# MDD.net
KiCad netlist of a schematic drawn in EAGLE
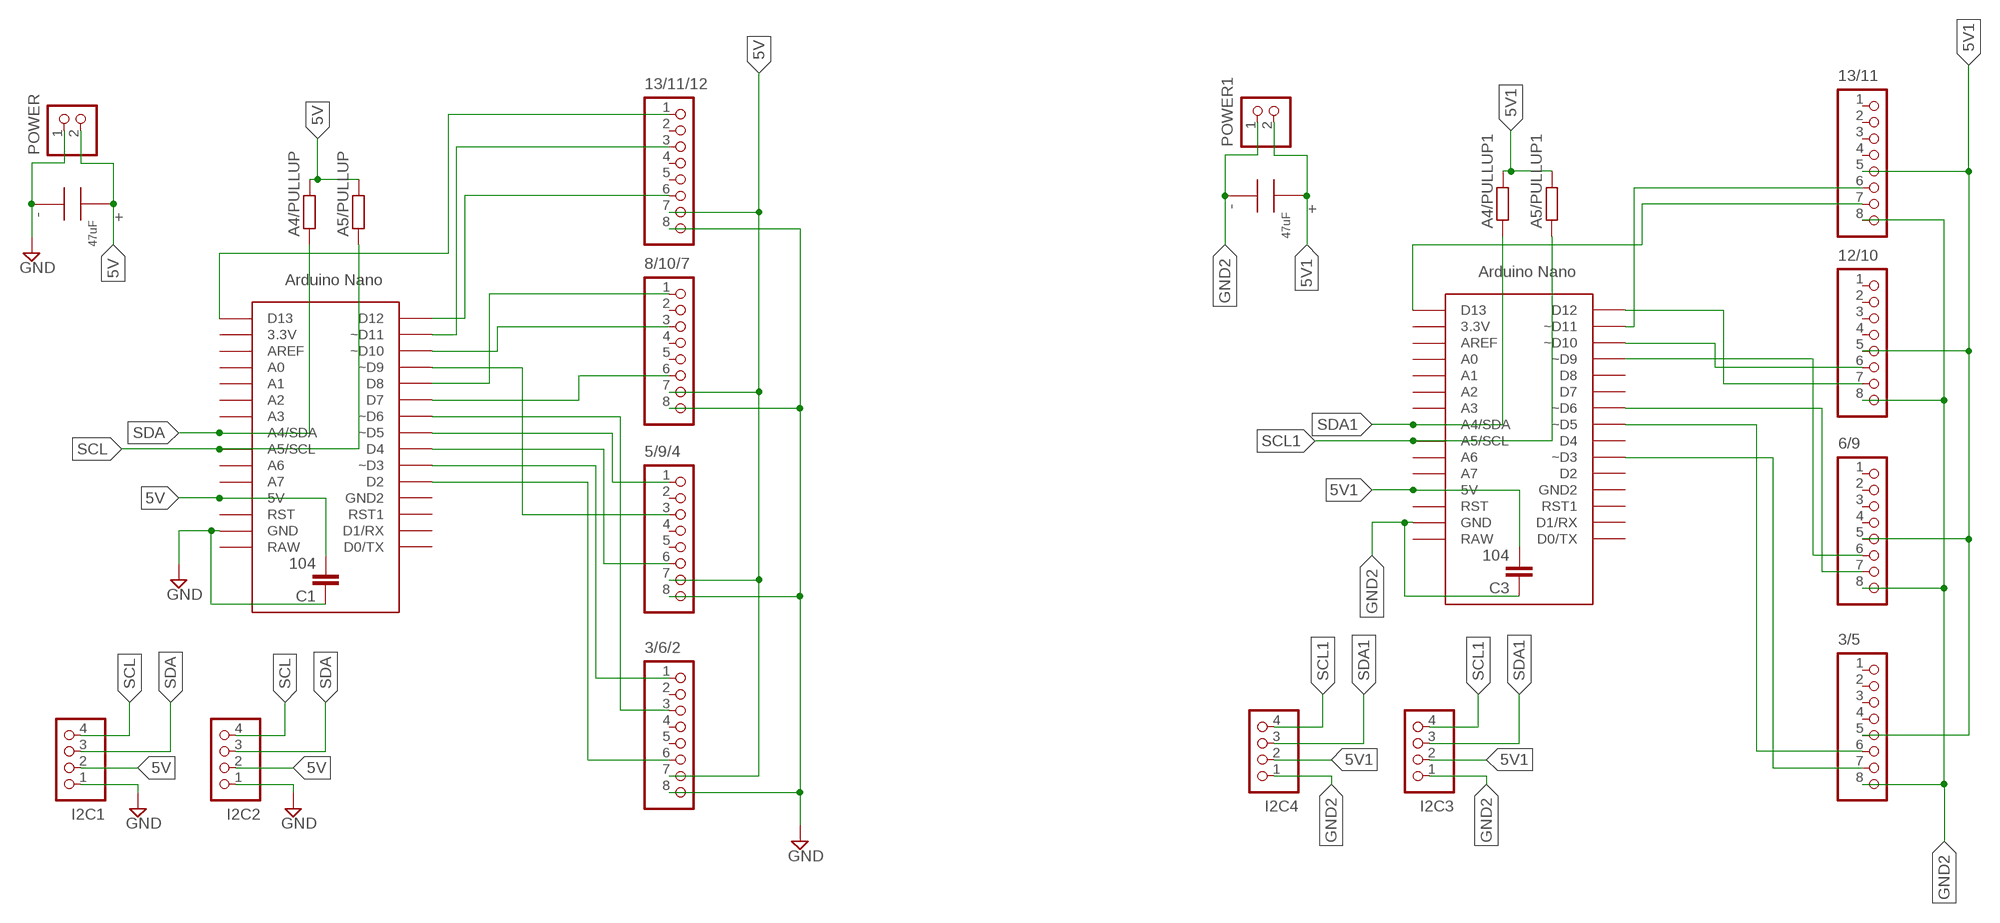
[diagram p0: schematic, sheet 1]

(export (version "E")
  (design (tool "Eeschema 10.0.6"))
  (components
    (comp (ref "3/5")
      (value "B8B-XH-A")
      (footprint "eagle-import:B8B-XH-A")
      (libsource (lib "eagle-import") (part "B8B-XH-A"))
    )
    (comp (ref "3/6/2")
      (value "B8B-XH-A")
      (footprint "eagle-import:B8B-XH-A")
      (libsource (lib "eagle-import") (part "B8B-XH-A"))
    )
    (comp (ref "5/9/4")
      (value "B8B-XH-A")
      (footprint "eagle-import:B8B-XH-A")
      (libsource (lib "eagle-import") (part "B8B-XH-A"))
    )
    (comp (ref "6/9")
      (value "B8B-XH-A")
      (footprint "eagle-import:B8B-XH-A")
      (libsource (lib "eagle-import") (part "B8B-XH-A"))
    )
    (comp (ref "8/10/7")
      (value "B8B-XH-A")
      (footprint "eagle-import:B8B-XH-A")
      (libsource (lib "eagle-import") (part "B8B-XH-A"))
    )
    (comp (ref "12/10")
      (value "B8B-XH-A")
      (footprint "eagle-import:B8B-XH-A")
      (libsource (lib "eagle-import") (part "B8B-XH-A"))
    )
    (comp (ref "13/11")
      (value "B8B-XH-A")
      (footprint "eagle-import:B8B-XH-A")
      (libsource (lib "eagle-import") (part "B8B-XH-A"))
    )
    (comp (ref "13/11/12")
      (value "B8B-XH-A")
      (footprint "eagle-import:B8B-XH-A")
      (libsource (lib "eagle-import") (part "B8B-XH-A"))
    )
    (comp (ref "A4/PULLUP")
      (value "R-EU_0204/7")
      (footprint "eagle-import:0204_7")
      (libsource (lib "eagle-import") (part "R-EU_0204/7"))
    )
    (comp (ref "A4/PULLUP1")
      (value "R-EU_0204/7")
      (footprint "eagle-import:0204_7")
      (libsource (lib "eagle-import") (part "R-EU_0204/7"))
    )
    (comp (ref "A5/PULLUP")
      (value "R-EU_0204/7")
      (footprint "eagle-import:0204_7")
      (libsource (lib "eagle-import") (part "R-EU_0204/7"))
    )
    (comp (ref "A5/PULLUP1")
      (value "R-EU_0204/7")
      (footprint "eagle-import:0204_7")
      (libsource (lib "eagle-import") (part "R-EU_0204/7"))
    )
    (comp (ref "C1")
      (value "104")
      (footprint "eagle-import:C2.5-2")
      (libsource (lib "eagle-import") (part "C2.5/2"))
    )
    (comp (ref "C2")
      (value "47uF")
      (footprint "eagle-import:C_47UF")
      (libsource (lib "eagle-import") (part "C_47UF"))
    )
    (comp (ref "C3")
      (value "104")
      (footprint "eagle-import:C2.5-2")
      (libsource (lib "eagle-import") (part "C2.5/2"))
    )
    (comp (ref "C4")
      (value "47uF")
      (footprint "eagle-import:C_47UF")
      (libsource (lib "eagle-import") (part "C_47UF"))
    )
    (comp (ref "I2C1")
      (value "B4B-XH-A")
      (footprint "eagle-import:B4B-XH-A")
      (libsource (lib "eagle-import") (part "B4B-XH-A"))
    )
    (comp (ref "I2C2")
      (value "B4B-XH-A")
      (footprint "eagle-import:B4B-XH-A")
      (libsource (lib "eagle-import") (part "B4B-XH-A"))
    )
    (comp (ref "I2C3")
      (value "B4B-XH-A")
      (footprint "eagle-import:B4B-XH-A")
      (libsource (lib "eagle-import") (part "B4B-XH-A"))
    )
    (comp (ref "I2C4")
      (value "B4B-XH-A")
      (footprint "eagle-import:B4B-XH-A")
      (libsource (lib "eagle-import") (part "B4B-XH-A"))
    )
    (comp (ref "NANO")
      (value "NANO")
      (footprint "eagle-import:NANO")
      (libsource (lib "eagle-import") (part "NANO"))
    )
    (comp (ref "NANO1")
      (value "NANO")
      (footprint "eagle-import:NANO")
      (libsource (lib "eagle-import") (part "NANO"))
    )
    (comp (ref "POWER")
      (value "B2B-XH-A")
      (footprint "eagle-import:B2B-XH-A")
      (libsource (lib "eagle-import") (part "B2B-XH-A"))
    )
    (comp (ref "POWER1")
      (value "B2B-XH-A")
      (footprint "eagle-import:B2B-XH-A")
      (libsource (lib "eagle-import") (part "B2B-XH-A"))
    )
  )
  (nets
    (net (code "1") (name "5V") (class "Default")
      (node (ref "13/11/12") (pin "7") (pinfunction "7_7") (pintype "passive"))
      (node (ref "3/6/2") (pin "7") (pinfunction "7_7") (pintype "passive"))
      (node (ref "5/9/4") (pin "7") (pinfunction "7_7") (pintype "passive"))
      (node (ref "8/10/7") (pin "7") (pinfunction "7_7") (pintype "passive"))
      (node (ref "A4/PULLUP") (pin "2") (pinfunction "2_2") (pintype "passive"))
      (node (ref "A5/PULLUP") (pin "2") (pinfunction "2_2") (pintype "passive"))
      (node (ref "C1") (pin "2") (pinfunction "2_2") (pintype "passive"))
      (node (ref "C2") (pin "+") (pinfunction "+_+") (pintype "bidirectional"))
      (node (ref "I2C1") (pin "2") (pinfunction "2_2") (pintype "passive"))
      (node (ref "I2C2") (pin "2") (pinfunction "2_2") (pintype "passive"))
      (node (ref "NANO") (pin "5V") (pinfunction "5V_5V") (pintype "bidirectional"))
      (node (ref "POWER") (pin "2") (pinfunction "VCC_2") (pintype "passive"))
    )
    (net (code "2") (name "5V1") (class "Default")
      (node (ref "12/10") (pin "5") (pinfunction "5_5") (pintype "passive"))
      (node (ref "13/11") (pin "5") (pinfunction "5_5") (pintype "passive"))
      (node (ref "3/5") (pin "5") (pinfunction "5_5") (pintype "passive"))
      (node (ref "6/9") (pin "5") (pinfunction "5_5") (pintype "passive"))
      (node (ref "A4/PULLUP1") (pin "2") (pinfunction "2_2") (pintype "passive"))
      (node (ref "A5/PULLUP1") (pin "2") (pinfunction "2_2") (pintype "passive"))
      (node (ref "C3") (pin "2") (pinfunction "2_2") (pintype "passive"))
      (node (ref "C4") (pin "+") (pinfunction "+_+") (pintype "bidirectional"))
      (node (ref "I2C3") (pin "2") (pinfunction "2_2") (pintype "passive"))
      (node (ref "I2C4") (pin "2") (pinfunction "2_2") (pintype "passive"))
      (node (ref "NANO1") (pin "5V") (pinfunction "5V_5V") (pintype "bidirectional"))
      (node (ref "POWER1") (pin "2") (pinfunction "VCC_2") (pintype "passive"))
    )
    (net (code "3") (name "GND") (class "Default")
      (node (ref "13/11/12") (pin "8") (pinfunction "8_8") (pintype "passive"))
      (node (ref "3/6/2") (pin "8") (pinfunction "8_8") (pintype "passive"))
      (node (ref "5/9/4") (pin "8") (pinfunction "8_8") (pintype "passive"))
      (node (ref "8/10/7") (pin "8") (pinfunction "8_8") (pintype "passive"))
      (node (ref "C1") (pin "1") (pinfunction "1_1") (pintype "passive"))
      (node (ref "C2") (pin "-") (pinfunction "-_-") (pintype "bidirectional"))
      (node (ref "I2C1") (pin "1") (pinfunction "1_1") (pintype "passive"))
      (node (ref "I2C2") (pin "1") (pinfunction "1_1") (pintype "passive"))
      (node (ref "NANO") (pin "GND") (pinfunction "GND_GND") (pintype "bidirectional"))
      (node (ref "POWER") (pin "1") (pinfunction "GND_1") (pintype "passive"))
    )
    (net (code "4") (name "GND2") (class "Default")
      (node (ref "12/10") (pin "8") (pinfunction "8_8") (pintype "passive"))
      (node (ref "13/11") (pin "8") (pinfunction "8_8") (pintype "passive"))
      (node (ref "3/5") (pin "8") (pinfunction "8_8") (pintype "passive"))
      (node (ref "6/9") (pin "8") (pinfunction "8_8") (pintype "passive"))
      (node (ref "C3") (pin "1") (pinfunction "1_1") (pintype "passive"))
      (node (ref "C4") (pin "-") (pinfunction "-_-") (pintype "bidirectional"))
      (node (ref "I2C3") (pin "1") (pinfunction "1_1") (pintype "passive"))
      (node (ref "I2C4") (pin "1") (pinfunction "1_1") (pintype "passive"))
      (node (ref "NANO1") (pin "GND") (pinfunction "GND_GND") (pintype "bidirectional"))
      (node (ref "POWER1") (pin "1") (pinfunction "GND_1") (pintype "passive"))
    )
    (net (code "5") (name "Net-(3/6/2-Pad6)") (class "Default")
      (node (ref "3/6/2") (pin "6") (pinfunction "6_6") (pintype "passive"))
      (node (ref "NANO") (pin "D2") (pinfunction "D2_D2") (pintype "bidirectional"))
    )
    (net (code "6") (name "Net-(5/9/4-Pad6)") (class "Default")
      (node (ref "5/9/4") (pin "6") (pinfunction "6_6") (pintype "passive"))
      (node (ref "NANO") (pin "D4") (pinfunction "D4_D4") (pintype "bidirectional"))
    )
    (net (code "7") (name "Net-(8/10/7-Pad1)") (class "Default")
      (node (ref "8/10/7") (pin "1") (pinfunction "1_1") (pintype "passive"))
      (node (ref "NANO") (pin "D8") (pinfunction "D8_D8") (pintype "bidirectional"))
    )
    (net (code "8") (name "Net-(8/10/7-Pad6)") (class "Default")
      (node (ref "8/10/7") (pin "6") (pinfunction "6_6") (pintype "passive"))
      (node (ref "NANO") (pin "D7") (pinfunction "D7_D7") (pintype "bidirectional"))
    )
    (net (code "9") (name "Net-(12/10-Pad7)") (class "Default")
      (node (ref "12/10") (pin "7") (pinfunction "7_7") (pintype "passive"))
      (node (ref "NANO1") (pin "D12") (pinfunction "D12_D12") (pintype "bidirectional"))
    )
    (net (code "10") (name "Net-(13/11-Pad7)") (class "Default")
      (node (ref "13/11") (pin "7") (pinfunction "7_7") (pintype "passive"))
      (node (ref "NANO1") (pin "D13") (pinfunction "D13_D13") (pintype "bidirectional"))
    )
    (net (code "11") (name "Net-(13/11/12-Pad1)") (class "Default")
      (node (ref "13/11/12") (pin "1") (pinfunction "1_1") (pintype "passive"))
      (node (ref "NANO") (pin "D13") (pinfunction "D13_D13") (pintype "bidirectional"))
    )
    (net (code "12") (name "Net-(13/11/12-Pad6)") (class "Default")
      (node (ref "13/11/12") (pin "6") (pinfunction "6_6") (pintype "passive"))
      (node (ref "NANO") (pin "D12") (pinfunction "D12_D12") (pintype "bidirectional"))
    )
    (net (code "13") (name "Net-(NANO-~{D3})") (class "Default")
      (node (ref "3/6/2") (pin "1") (pinfunction "1_1") (pintype "passive"))
      (node (ref "NANO") (pin "D3") (pinfunction "~{D3}_D3") (pintype "bidirectional"))
    )
    (net (code "14") (name "Net-(NANO-~{D5})") (class "Default")
      (node (ref "5/9/4") (pin "1") (pinfunction "1_1") (pintype "passive"))
      (node (ref "NANO") (pin "D5") (pinfunction "~{D5}_D5") (pintype "bidirectional"))
    )
    (net (code "15") (name "Net-(NANO-~{D6})") (class "Default")
      (node (ref "3/6/2") (pin "3") (pinfunction "3_3") (pintype "passive"))
      (node (ref "NANO") (pin "D6") (pinfunction "~{D6}_D6") (pintype "bidirectional"))
    )
    (net (code "16") (name "Net-(NANO-~{D9})") (class "Default")
      (node (ref "5/9/4") (pin "3") (pinfunction "3_3") (pintype "passive"))
      (node (ref "NANO") (pin "D9") (pinfunction "~{D9}_D9") (pintype "bidirectional"))
    )
    (net (code "17") (name "Net-(NANO-~{D10})") (class "Default")
      (node (ref "8/10/7") (pin "3") (pinfunction "3_3") (pintype "passive"))
      (node (ref "NANO") (pin "D10") (pinfunction "~{D10}_D10") (pintype "bidirectional"))
    )
    (net (code "18") (name "Net-(NANO-~{D11})") (class "Default")
      (node (ref "13/11/12") (pin "3") (pinfunction "3_3") (pintype "passive"))
      (node (ref "NANO") (pin "D11") (pinfunction "~{D11}_D11") (pintype "bidirectional"))
    )
    (net (code "19") (name "Net-(NANO1-~{D3})") (class "Default")
      (node (ref "3/5") (pin "7") (pinfunction "7_7") (pintype "passive"))
      (node (ref "NANO1") (pin "D3") (pinfunction "~{D3}_D3") (pintype "bidirectional"))
    )
    (net (code "20") (name "Net-(NANO1-~{D5})") (class "Default")
      (node (ref "3/5") (pin "6") (pinfunction "6_6") (pintype "passive"))
      (node (ref "NANO1") (pin "D5") (pinfunction "~{D5}_D5") (pintype "bidirectional"))
    )
    (net (code "21") (name "Net-(NANO1-~{D6})") (class "Default")
      (node (ref "6/9") (pin "7") (pinfunction "7_7") (pintype "passive"))
      (node (ref "NANO1") (pin "D6") (pinfunction "~{D6}_D6") (pintype "bidirectional"))
    )
    (net (code "22") (name "Net-(NANO1-~{D9})") (class "Default")
      (node (ref "6/9") (pin "6") (pinfunction "6_6") (pintype "passive"))
      (node (ref "NANO1") (pin "D9") (pinfunction "~{D9}_D9") (pintype "bidirectional"))
    )
    (net (code "23") (name "Net-(NANO1-~{D10})") (class "Default")
      (node (ref "12/10") (pin "6") (pinfunction "6_6") (pintype "passive"))
      (node (ref "NANO1") (pin "D10") (pinfunction "~{D10}_D10") (pintype "bidirectional"))
    )
    (net (code "24") (name "Net-(NANO1-~{D11})") (class "Default")
      (node (ref "13/11") (pin "6") (pinfunction "6_6") (pintype "passive"))
      (node (ref "NANO1") (pin "D11") (pinfunction "~{D11}_D11") (pintype "bidirectional"))
    )
    (net (code "25") (name "SCL") (class "Default")
      (node (ref "A5/PULLUP") (pin "1") (pinfunction "1_1") (pintype "passive"))
      (node (ref "I2C1") (pin "4") (pinfunction "4_4") (pintype "passive"))
      (node (ref "I2C2") (pin "4") (pinfunction "4_4") (pintype "passive"))
      (node (ref "NANO") (pin "A5") (pinfunction "A5/SCL_A5") (pintype "bidirectional"))
    )
    (net (code "26") (name "SCL1") (class "Default")
      (node (ref "A5/PULLUP1") (pin "1") (pinfunction "1_1") (pintype "passive"))
      (node (ref "I2C3") (pin "4") (pinfunction "4_4") (pintype "passive"))
      (node (ref "I2C4") (pin "4") (pinfunction "4_4") (pintype "passive"))
      (node (ref "NANO1") (pin "A5") (pinfunction "A5/SCL_A5") (pintype "bidirectional"))
    )
    (net (code "27") (name "SDA") (class "Default")
      (node (ref "A4/PULLUP") (pin "1") (pinfunction "1_1") (pintype "passive"))
      (node (ref "I2C1") (pin "3") (pinfunction "3_3") (pintype "passive"))
      (node (ref "I2C2") (pin "3") (pinfunction "3_3") (pintype "passive"))
      (node (ref "NANO") (pin "A4") (pinfunction "A4/SDA_A4") (pintype "bidirectional"))
    )
    (net (code "28") (name "SDA1") (class "Default")
      (node (ref "A4/PULLUP1") (pin "1") (pinfunction "1_1") (pintype "passive"))
      (node (ref "I2C3") (pin "3") (pinfunction "3_3") (pintype "passive"))
      (node (ref "I2C4") (pin "3") (pinfunction "3_3") (pintype "passive"))
      (node (ref "NANO1") (pin "A4") (pinfunction "A4/SDA_A4") (pintype "bidirectional"))
    )
    (net (code "29") (name "unconnected-(3/5-Pad1)") (class "Default")
      (node (ref "3/5") (pin "1") (pinfunction "1_1") (pintype "passive"))
    )
    (net (code "30") (name "unconnected-(3/5-Pad2)") (class "Default")
      (node (ref "3/5") (pin "2") (pinfunction "2_2") (pintype "passive"))
    )
    (net (code "31") (name "unconnected-(3/5-Pad3)") (class "Default")
      (node (ref "3/5") (pin "3") (pinfunction "3_3") (pintype "passive"))
    )
    (net (code "32") (name "unconnected-(3/5-Pad4)") (class "Default")
      (node (ref "3/5") (pin "4") (pinfunction "4_4") (pintype "passive"))
    )
    (net (code "33") (name "unconnected-(3/6/2-Pad2)") (class "Default")
      (node (ref "3/6/2") (pin "2") (pinfunction "2_2") (pintype "passive"))
    )
    (net (code "34") (name "unconnected-(3/6/2-Pad4)") (class "Default")
      (node (ref "3/6/2") (pin "4") (pinfunction "4_4") (pintype "passive"))
    )
    (net (code "35") (name "unconnected-(3/6/2-Pad5)") (class "Default")
      (node (ref "3/6/2") (pin "5") (pinfunction "5_5") (pintype "passive"))
    )
    (net (code "36") (name "unconnected-(5/9/4-Pad2)") (class "Default")
      (node (ref "5/9/4") (pin "2") (pinfunction "2_2") (pintype "passive"))
    )
    (net (code "37") (name "unconnected-(5/9/4-Pad4)") (class "Default")
      (node (ref "5/9/4") (pin "4") (pinfunction "4_4") (pintype "passive"))
    )
    (net (code "38") (name "unconnected-(5/9/4-Pad5)") (class "Default")
      (node (ref "5/9/4") (pin "5") (pinfunction "5_5") (pintype "passive"))
    )
    (net (code "39") (name "unconnected-(6/9-Pad1)") (class "Default")
      (node (ref "6/9") (pin "1") (pinfunction "1_1") (pintype "passive"))
    )
    (net (code "40") (name "unconnected-(6/9-Pad2)") (class "Default")
      (node (ref "6/9") (pin "2") (pinfunction "2_2") (pintype "passive"))
    )
    (net (code "41") (name "unconnected-(6/9-Pad3)") (class "Default")
      (node (ref "6/9") (pin "3") (pinfunction "3_3") (pintype "passive"))
    )
    (net (code "42") (name "unconnected-(6/9-Pad4)") (class "Default")
      (node (ref "6/9") (pin "4") (pinfunction "4_4") (pintype "passive"))
    )
    (net (code "43") (name "unconnected-(8/10/7-Pad2)") (class "Default")
      (node (ref "8/10/7") (pin "2") (pinfunction "2_2") (pintype "passive"))
    )
    (net (code "44") (name "unconnected-(8/10/7-Pad4)") (class "Default")
      (node (ref "8/10/7") (pin "4") (pinfunction "4_4") (pintype "passive"))
    )
    (net (code "45") (name "unconnected-(8/10/7-Pad5)") (class "Default")
      (node (ref "8/10/7") (pin "5") (pinfunction "5_5") (pintype "passive"))
    )
    (net (code "46") (name "unconnected-(12/10-Pad1)") (class "Default")
      (node (ref "12/10") (pin "1") (pinfunction "1_1") (pintype "passive"))
    )
    (net (code "47") (name "unconnected-(12/10-Pad2)") (class "Default")
      (node (ref "12/10") (pin "2") (pinfunction "2_2") (pintype "passive"))
    )
    (net (code "48") (name "unconnected-(12/10-Pad3)") (class "Default")
      (node (ref "12/10") (pin "3") (pinfunction "3_3") (pintype "passive"))
    )
    (net (code "49") (name "unconnected-(12/10-Pad4)") (class "Default")
      (node (ref "12/10") (pin "4") (pinfunction "4_4") (pintype "passive"))
    )
    (net (code "50") (name "unconnected-(13/11-Pad1)") (class "Default")
      (node (ref "13/11") (pin "1") (pinfunction "1_1") (pintype "passive"))
    )
    (net (code "51") (name "unconnected-(13/11-Pad2)") (class "Default")
      (node (ref "13/11") (pin "2") (pinfunction "2_2") (pintype "passive"))
    )
    (net (code "52") (name "unconnected-(13/11-Pad3)") (class "Default")
      (node (ref "13/11") (pin "3") (pinfunction "3_3") (pintype "passive"))
    )
    (net (code "53") (name "unconnected-(13/11-Pad4)") (class "Default")
      (node (ref "13/11") (pin "4") (pinfunction "4_4") (pintype "passive"))
    )
    (net (code "54") (name "unconnected-(13/11/12-Pad2)") (class "Default")
      (node (ref "13/11/12") (pin "2") (pinfunction "2_2") (pintype "passive"))
    )
    (net (code "55") (name "unconnected-(13/11/12-Pad4)") (class "Default")
      (node (ref "13/11/12") (pin "4") (pinfunction "4_4") (pintype "passive"))
    )
    (net (code "56") (name "unconnected-(13/11/12-Pad5)") (class "Default")
      (node (ref "13/11/12") (pin "5") (pinfunction "5_5") (pintype "passive"))
    )
    (net (code "57") (name "unconnected-(NANO-D0{slash}TX-PadTX0)") (class "Default")
      (node (ref "NANO") (pin "TX0") (pinfunction "D0/TX_TX0") (pintype "bidirectional"))
    )
    (net (code "58") (name "unconnected-(NANO-D1{slash}RX-PadRX1)") (class "Default")
      (node (ref "NANO") (pin "RX1") (pinfunction "D1/RX_RX1") (pintype "bidirectional"))
    )
    (net (code "59") (name "unconnected-(NANO-GND2-PadGND1)") (class "Default")
      (node (ref "NANO") (pin "GND1") (pinfunction "GND2_GND1") (pintype "bidirectional"))
    )
    (net (code "60") (name "unconnected-(NANO-Pad3.3V)") (class "Default")
      (node (ref "NANO") (pin "3.3V") (pinfunction "3.3V_3.3V") (pintype "bidirectional"))
    )
    (net (code "61") (name "unconnected-(NANO-PadA0)") (class "Default")
      (node (ref "NANO") (pin "A0") (pinfunction "A0_A0") (pintype "bidirectional"))
    )
    (net (code "62") (name "unconnected-(NANO-PadA1)") (class "Default")
      (node (ref "NANO") (pin "A1") (pinfunction "A1_A1") (pintype "bidirectional"))
    )
    (net (code "63") (name "unconnected-(NANO-PadA2)") (class "Default")
      (node (ref "NANO") (pin "A2") (pinfunction "A2_A2") (pintype "bidirectional"))
    )
    (net (code "64") (name "unconnected-(NANO-PadA3)") (class "Default")
      (node (ref "NANO") (pin "A3") (pinfunction "A3_A3") (pintype "bidirectional"))
    )
    (net (code "65") (name "unconnected-(NANO-PadA6)") (class "Default")
      (node (ref "NANO") (pin "A6") (pinfunction "A6_A6") (pintype "bidirectional"))
    )
    (net (code "66") (name "unconnected-(NANO-PadA7)") (class "Default")
      (node (ref "NANO") (pin "A7") (pinfunction "A7_A7") (pintype "bidirectional"))
    )
    (net (code "67") (name "unconnected-(NANO-PadAREF)") (class "Default")
      (node (ref "NANO") (pin "AREF") (pinfunction "AREF_AREF") (pintype "bidirectional"))
    )
    (net (code "68") (name "unconnected-(NANO-PadRAW)") (class "Default")
      (node (ref "NANO") (pin "RAW") (pinfunction "RAW_RAW") (pintype "bidirectional"))
    )
    (net (code "69") (name "unconnected-(NANO-PadRST)") (class "Default")
      (node (ref "NANO") (pin "RST") (pinfunction "RST_RST") (pintype "bidirectional"))
    )
    (net (code "70") (name "unconnected-(NANO-PadRST1)") (class "Default")
      (node (ref "NANO") (pin "RST1") (pinfunction "RST1_RST1") (pintype "bidirectional"))
    )
    (net (code "71") (name "unconnected-(NANO1-D0{slash}TX-PadTX0)") (class "Default")
      (node (ref "NANO1") (pin "TX0") (pinfunction "D0/TX_TX0") (pintype "bidirectional"))
    )
    (net (code "72") (name "unconnected-(NANO1-D1{slash}RX-PadRX1)") (class "Default")
      (node (ref "NANO1") (pin "RX1") (pinfunction "D1/RX_RX1") (pintype "bidirectional"))
    )
    (net (code "73") (name "unconnected-(NANO1-GND2-PadGND1)") (class "Default")
      (node (ref "NANO1") (pin "GND1") (pinfunction "GND2_GND1") (pintype "bidirectional"))
    )
    (net (code "74") (name "unconnected-(NANO1-Pad3.3V)") (class "Default")
      (node (ref "NANO1") (pin "3.3V") (pinfunction "3.3V_3.3V") (pintype "bidirectional"))
    )
    (net (code "75") (name "unconnected-(NANO1-PadA0)") (class "Default")
      (node (ref "NANO1") (pin "A0") (pinfunction "A0_A0") (pintype "bidirectional"))
    )
    (net (code "76") (name "unconnected-(NANO1-PadA1)") (class "Default")
      (node (ref "NANO1") (pin "A1") (pinfunction "A1_A1") (pintype "bidirectional"))
    )
    (net (code "77") (name "unconnected-(NANO1-PadA2)") (class "Default")
      (node (ref "NANO1") (pin "A2") (pinfunction "A2_A2") (pintype "bidirectional"))
    )
    (net (code "78") (name "unconnected-(NANO1-PadA3)") (class "Default")
      (node (ref "NANO1") (pin "A3") (pinfunction "A3_A3") (pintype "bidirectional"))
    )
    (net (code "79") (name "unconnected-(NANO1-PadA6)") (class "Default")
      (node (ref "NANO1") (pin "A6") (pinfunction "A6_A6") (pintype "bidirectional"))
    )
    (net (code "80") (name "unconnected-(NANO1-PadA7)") (class "Default")
      (node (ref "NANO1") (pin "A7") (pinfunction "A7_A7") (pintype "bidirectional"))
    )
    (net (code "81") (name "unconnected-(NANO1-PadAREF)") (class "Default")
      (node (ref "NANO1") (pin "AREF") (pinfunction "AREF_AREF") (pintype "bidirectional"))
    )
    (net (code "82") (name "unconnected-(NANO1-PadD2)") (class "Default")
      (node (ref "NANO1") (pin "D2") (pinfunction "D2_D2") (pintype "bidirectional"))
    )
    (net (code "83") (name "unconnected-(NANO1-PadD4)") (class "Default")
      (node (ref "NANO1") (pin "D4") (pinfunction "D4_D4") (pintype "bidirectional"))
    )
    (net (code "84") (name "unconnected-(NANO1-PadD7)") (class "Default")
      (node (ref "NANO1") (pin "D7") (pinfunction "D7_D7") (pintype "bidirectional"))
    )
    (net (code "85") (name "unconnected-(NANO1-PadD8)") (class "Default")
      (node (ref "NANO1") (pin "D8") (pinfunction "D8_D8") (pintype "bidirectional"))
    )
    (net (code "86") (name "unconnected-(NANO1-PadRAW)") (class "Default")
      (node (ref "NANO1") (pin "RAW") (pinfunction "RAW_RAW") (pintype "bidirectional"))
    )
    (net (code "87") (name "unconnected-(NANO1-PadRST)") (class "Default")
      (node (ref "NANO1") (pin "RST") (pinfunction "RST_RST") (pintype "bidirectional"))
    )
    (net (code "88") (name "unconnected-(NANO1-PadRST1)") (class "Default")
      (node (ref "NANO1") (pin "RST1") (pinfunction "RST1_RST1") (pintype "bidirectional"))
    )
  )
)
